# amp_board.net
KiCad netlist of a schematic drawn in EAGLE
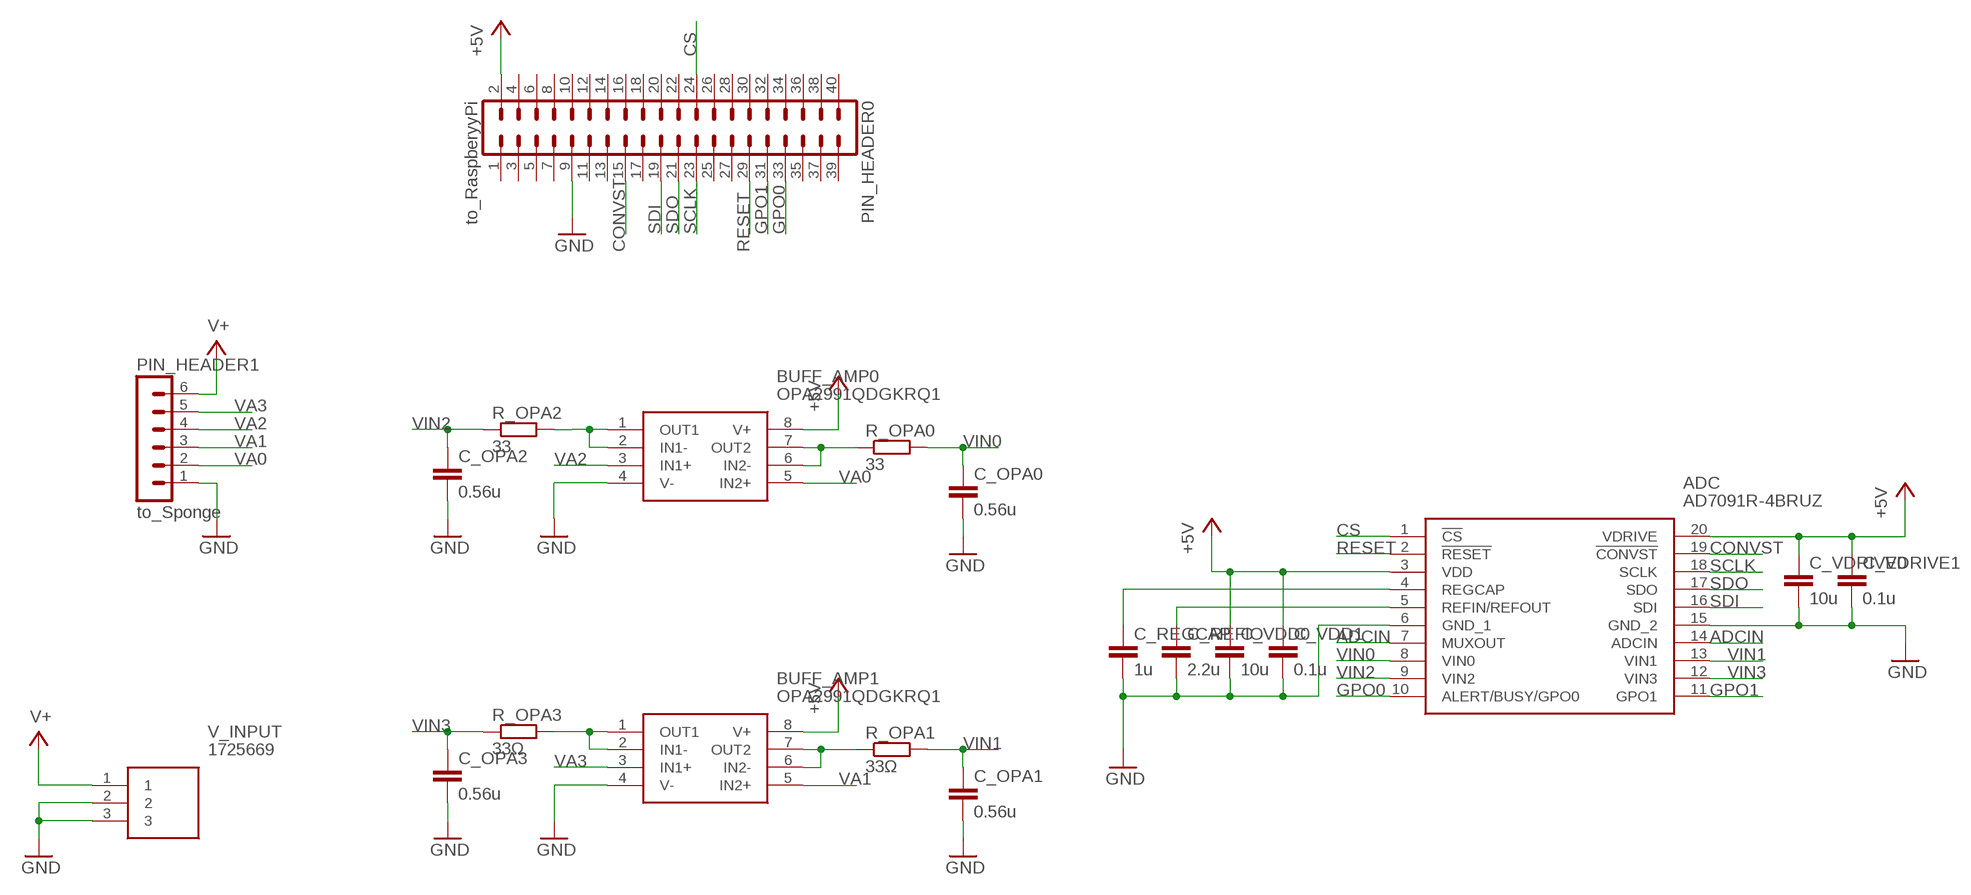
[diagram p0: schematic, sheet 1]

(export (version "E")
  (design (tool "Eeschema 10.0.6"))
  (components
    (comp (ref "ADC")
      (value "AD7091R-4BRUZ")
      (footprint "eagle-import:SOP65P640X120-20N")
      (fields (field (name "RS_PART_NUMBER") "8107727P"))
      (libsource (lib "eagle-import") (part "AD7091R-4BRUZ"))
    )
    (comp (ref "BUFF_AMP0")
      (value "OPA2991QDGKRQ1")
      (footprint "eagle-import:SOP65P490X110-8N")
      (libsource (lib "eagle-import") (part "OPA2991QDGKRQ1"))
    )
    (comp (ref "BUFF_AMP1")
      (value "OPA2991QDGKRQ1")
      (footprint "eagle-import:SOP65P490X110-8N")
      (libsource (lib "eagle-import") (part "OPA2991QDGKRQ1"))
    )
    (comp (ref "C_OPA0")
      (value "0.56u")
      (footprint "eagle-import:C0805")
      (libsource (lib "eagle-import") (part "C-EUC0805"))
    )
    (comp (ref "C_OPA1")
      (value "0.56u")
      (footprint "eagle-import:C0805")
      (libsource (lib "eagle-import") (part "C-EUC0805"))
    )
    (comp (ref "C_OPA2")
      (value "0.56u")
      (footprint "eagle-import:C0805")
      (libsource (lib "eagle-import") (part "C-EUC0805"))
    )
    (comp (ref "C_OPA3")
      (value "0.56u")
      (footprint "eagle-import:C0805")
      (libsource (lib "eagle-import") (part "C-EUC0805"))
    )
    (comp (ref "C_REFIO")
      (value "2.2u")
      (footprint "eagle-import:C0805")
      (libsource (lib "eagle-import") (part "C-EUC0805"))
    )
    (comp (ref "C_REGCAP")
      (value "1u")
      (footprint "eagle-import:C0805")
      (libsource (lib "eagle-import") (part "C-EUC0805"))
    )
    (comp (ref "C_VDD0")
      (value "10u")
      (footprint "eagle-import:C0805")
      (libsource (lib "eagle-import") (part "C-EUC0805"))
    )
    (comp (ref "C_VDD1")
      (value "0.1u")
      (footprint "eagle-import:C0805")
      (libsource (lib "eagle-import") (part "C-EUC0805"))
    )
    (comp (ref "C_VDRIVE0")
      (value "10u")
      (footprint "eagle-import:C0805")
      (libsource (lib "eagle-import") (part "C-EUC0805"))
    )
    (comp (ref "C_VDRIVE1")
      (value "0.1u")
      (footprint "eagle-import:C0805")
      (libsource (lib "eagle-import") (part "C-EUC0805"))
    )
    (comp (ref "PIN_HEADER0")
      (value "to_RaspberyyPi")
      (footprint "eagle-import:MA20-2")
      (libsource (lib "eagle-import") (part "MA20-2"))
    )
    (comp (ref "PIN_HEADER1")
      (value "to_Sponge")
      (footprint "eagle-import:MA06-1")
      (libsource (lib "eagle-import") (part "MA06-1"))
    )
    (comp (ref "R_OPA0")
      (value "33")
      (footprint "eagle-import:R1206")
      (libsource (lib "eagle-import") (part "R-EU_R1206"))
    )
    (comp (ref "R_OPA1")
      (value "33Ω")
      (footprint "eagle-import:R1206")
      (libsource (lib "eagle-import") (part "R-EU_R1206"))
    )
    (comp (ref "R_OPA2")
      (value "33")
      (footprint "eagle-import:R1206")
      (libsource (lib "eagle-import") (part "R-EU_R1206"))
    )
    (comp (ref "R_OPA3")
      (value "33Ω")
      (footprint "eagle-import:R1206")
      (libsource (lib "eagle-import") (part "R-EU_R1206"))
    )
    (comp (ref "V_INPUT")
      (value "1725669")
      (footprint "eagle-import:1725669")
      (fields (field (name "MOUSER_PART_NUMBER") "651-1725669"))
      (libsource (lib "eagle-import") (part "1725669"))
    )
  )
  (nets
    (net (code "1") (name "+5V") (class "Default")
      (node (ref "ADC") (pin "20") (pinfunction "VDRIVE_20") (pintype "bidirectional"))
      (node (ref "ADC") (pin "3") (pinfunction "VDD_3") (pintype "bidirectional"))
      (node (ref "BUFF_AMP0") (pin "8") (pinfunction "V+_8") (pintype "bidirectional"))
      (node (ref "BUFF_AMP1") (pin "8") (pinfunction "V+_8") (pintype "bidirectional"))
      (node (ref "C_VDD0") (pin "1") (pinfunction "1_1") (pintype "passive"))
      (node (ref "C_VDD1") (pin "1") (pinfunction "1_1") (pintype "passive"))
      (node (ref "C_VDRIVE0") (pin "1") (pinfunction "1_1") (pintype "passive"))
      (node (ref "C_VDRIVE1") (pin "1") (pinfunction "1_1") (pintype "passive"))
      (node (ref "PIN_HEADER0") (pin "2") (pinfunction "2_2") (pintype "passive"))
    )
    (net (code "2") (name "/ADCIN") (class "Default")
      (node (ref "ADC") (pin "14") (pinfunction "ADCIN_14") (pintype "bidirectional"))
      (node (ref "ADC") (pin "7") (pinfunction "MUXOUT_7") (pintype "bidirectional"))
    )
    (net (code "3") (name "/CONVST") (class "Default")
      (node (ref "ADC") (pin "19") (pinfunction "~{CONVST}_19") (pintype "bidirectional"))
      (node (ref "PIN_HEADER0") (pin "15") (pinfunction "15_15") (pintype "passive"))
    )
    (net (code "4") (name "/CS") (class "Default")
      (node (ref "ADC") (pin "1") (pinfunction "~{CS}_1") (pintype "bidirectional"))
      (node (ref "PIN_HEADER0") (pin "24") (pinfunction "24_24") (pintype "passive"))
    )
    (net (code "5") (name "/GPO0") (class "Default")
      (node (ref "ADC") (pin "10") (pinfunction "ALERT/BUSY/GPO0_10") (pintype "bidirectional"))
      (node (ref "PIN_HEADER0") (pin "33") (pinfunction "33_33") (pintype "passive"))
    )
    (net (code "6") (name "/GPO1") (class "Default")
      (node (ref "ADC") (pin "11") (pinfunction "GPO1_11") (pintype "bidirectional"))
      (node (ref "PIN_HEADER0") (pin "31") (pinfunction "31_31") (pintype "passive"))
    )
    (net (code "7") (name "/RESET") (class "Default")
      (node (ref "ADC") (pin "2") (pinfunction "~{RESET}_2") (pintype "bidirectional"))
      (node (ref "PIN_HEADER0") (pin "29") (pinfunction "29_29") (pintype "passive"))
    )
    (net (code "8") (name "/SCLK") (class "Default")
      (node (ref "ADC") (pin "18") (pinfunction "SCLK_18") (pintype "bidirectional"))
      (node (ref "PIN_HEADER0") (pin "23") (pinfunction "23_23") (pintype "passive"))
    )
    (net (code "9") (name "/SDI") (class "Default")
      (node (ref "ADC") (pin "16") (pinfunction "SDI_16") (pintype "bidirectional"))
      (node (ref "PIN_HEADER0") (pin "19") (pinfunction "19_19") (pintype "passive"))
    )
    (net (code "10") (name "/SDO") (class "Default")
      (node (ref "ADC") (pin "17") (pinfunction "SDO_17") (pintype "bidirectional"))
      (node (ref "PIN_HEADER0") (pin "21") (pinfunction "21_21") (pintype "passive"))
    )
    (net (code "11") (name "/VA0") (class "Default")
      (node (ref "BUFF_AMP0") (pin "5") (pinfunction "IN2+_5") (pintype "bidirectional"))
      (node (ref "PIN_HEADER1") (pin "2") (pinfunction "2_2") (pintype "passive"))
    )
    (net (code "12") (name "/VA1") (class "Default")
      (node (ref "BUFF_AMP1") (pin "5") (pinfunction "IN2+_5") (pintype "bidirectional"))
      (node (ref "PIN_HEADER1") (pin "3") (pinfunction "3_3") (pintype "passive"))
    )
    (net (code "13") (name "/VA2") (class "Default")
      (node (ref "BUFF_AMP0") (pin "3") (pinfunction "IN1+_3") (pintype "bidirectional"))
      (node (ref "PIN_HEADER1") (pin "4") (pinfunction "4_4") (pintype "passive"))
    )
    (net (code "14") (name "/VA3") (class "Default")
      (node (ref "BUFF_AMP1") (pin "3") (pinfunction "IN1+_3") (pintype "bidirectional"))
      (node (ref "PIN_HEADER1") (pin "5") (pinfunction "5_5") (pintype "passive"))
    )
    (net (code "15") (name "/VIN0") (class "Default")
      (node (ref "ADC") (pin "8") (pinfunction "VIN0_8") (pintype "bidirectional"))
      (node (ref "C_OPA0") (pin "1") (pinfunction "1_1") (pintype "passive"))
      (node (ref "R_OPA0") (pin "2") (pinfunction "2_2") (pintype "passive"))
    )
    (net (code "16") (name "/VIN1") (class "Default")
      (node (ref "ADC") (pin "13") (pinfunction "VIN1_13") (pintype "bidirectional"))
      (node (ref "C_OPA1") (pin "1") (pinfunction "1_1") (pintype "passive"))
      (node (ref "R_OPA1") (pin "2") (pinfunction "2_2") (pintype "passive"))
    )
    (net (code "17") (name "/VIN2") (class "Default")
      (node (ref "ADC") (pin "9") (pinfunction "VIN2_9") (pintype "bidirectional"))
      (node (ref "C_OPA2") (pin "1") (pinfunction "1_1") (pintype "passive"))
      (node (ref "R_OPA2") (pin "1") (pinfunction "1_1") (pintype "passive"))
    )
    (net (code "18") (name "/VIN3") (class "Default")
      (node (ref "ADC") (pin "12") (pinfunction "VIN3_12") (pintype "bidirectional"))
      (node (ref "C_OPA3") (pin "1") (pinfunction "1_1") (pintype "passive"))
      (node (ref "R_OPA3") (pin "1") (pinfunction "1_1") (pintype "passive"))
    )
    (net (code "19") (name "GND") (class "Default")
      (node (ref "ADC") (pin "15") (pinfunction "GND_2_15") (pintype "bidirectional"))
      (node (ref "ADC") (pin "6") (pinfunction "GND_1_6") (pintype "bidirectional"))
      (node (ref "BUFF_AMP0") (pin "4") (pinfunction "V-_4") (pintype "bidirectional"))
      (node (ref "BUFF_AMP1") (pin "4") (pinfunction "V-_4") (pintype "bidirectional"))
      (node (ref "C_OPA0") (pin "2") (pinfunction "2_2") (pintype "passive"))
      (node (ref "C_OPA1") (pin "2") (pinfunction "2_2") (pintype "passive"))
      (node (ref "C_OPA2") (pin "2") (pinfunction "2_2") (pintype "passive"))
      (node (ref "C_OPA3") (pin "2") (pinfunction "2_2") (pintype "passive"))
      (node (ref "C_REFIO") (pin "2") (pinfunction "2_2") (pintype "passive"))
      (node (ref "C_REGCAP") (pin "2") (pinfunction "2_2") (pintype "passive"))
      (node (ref "C_VDD0") (pin "2") (pinfunction "2_2") (pintype "passive"))
      (node (ref "C_VDD1") (pin "2") (pinfunction "2_2") (pintype "passive"))
      (node (ref "C_VDRIVE0") (pin "2") (pinfunction "2_2") (pintype "passive"))
      (node (ref "C_VDRIVE1") (pin "2") (pinfunction "2_2") (pintype "passive"))
      (node (ref "PIN_HEADER0") (pin "9") (pinfunction "9_9") (pintype "passive"))
      (node (ref "PIN_HEADER1") (pin "1") (pinfunction "1_1") (pintype "passive"))
      (node (ref "V_INPUT") (pin "2") (pinfunction "2_2") (pintype "bidirectional"))
      (node (ref "V_INPUT") (pin "3") (pinfunction "3_3") (pintype "bidirectional"))
    )
    (net (code "20") (name "Net-(ADC-REFIN{slash}REFOUT)") (class "Default")
      (node (ref "ADC") (pin "5") (pinfunction "REFIN/REFOUT_5") (pintype "bidirectional"))
      (node (ref "C_REFIO") (pin "1") (pinfunction "1_1") (pintype "passive"))
    )
    (net (code "21") (name "Net-(ADC-REGCAP)") (class "Default")
      (node (ref "ADC") (pin "4") (pinfunction "REGCAP_4") (pintype "bidirectional"))
      (node (ref "C_REGCAP") (pin "1") (pinfunction "1_1") (pintype "passive"))
    )
    (net (code "22") (name "Net-(BUFF_AMP0-IN1-)") (class "Default")
      (node (ref "BUFF_AMP0") (pin "1") (pinfunction "OUT1_1") (pintype "bidirectional"))
      (node (ref "BUFF_AMP0") (pin "2") (pinfunction "IN1-_2") (pintype "bidirectional"))
      (node (ref "R_OPA2") (pin "2") (pinfunction "2_2") (pintype "passive"))
    )
    (net (code "23") (name "Net-(BUFF_AMP0-IN2-)") (class "Default")
      (node (ref "BUFF_AMP0") (pin "6") (pinfunction "IN2-_6") (pintype "bidirectional"))
      (node (ref "BUFF_AMP0") (pin "7") (pinfunction "OUT2_7") (pintype "bidirectional"))
      (node (ref "R_OPA0") (pin "1") (pinfunction "1_1") (pintype "passive"))
    )
    (net (code "24") (name "Net-(BUFF_AMP1-IN1-)") (class "Default")
      (node (ref "BUFF_AMP1") (pin "1") (pinfunction "OUT1_1") (pintype "bidirectional"))
      (node (ref "BUFF_AMP1") (pin "2") (pinfunction "IN1-_2") (pintype "bidirectional"))
      (node (ref "R_OPA3") (pin "2") (pinfunction "2_2") (pintype "passive"))
    )
    (net (code "25") (name "Net-(BUFF_AMP1-IN2-)") (class "Default")
      (node (ref "BUFF_AMP1") (pin "6") (pinfunction "IN2-_6") (pintype "bidirectional"))
      (node (ref "BUFF_AMP1") (pin "7") (pinfunction "OUT2_7") (pintype "bidirectional"))
      (node (ref "R_OPA1") (pin "1") (pinfunction "1_1") (pintype "passive"))
    )
    (net (code "26") (name "V+") (class "Default")
      (node (ref "PIN_HEADER1") (pin "6") (pinfunction "6_6") (pintype "passive"))
      (node (ref "V_INPUT") (pin "1") (pinfunction "1_1") (pintype "bidirectional"))
    )
    (net (code "27") (name "unconnected-(PIN_HEADER0-Pad1)") (class "Default")
      (node (ref "PIN_HEADER0") (pin "1") (pinfunction "1_1") (pintype "passive"))
    )
    (net (code "28") (name "unconnected-(PIN_HEADER0-Pad3)") (class "Default")
      (node (ref "PIN_HEADER0") (pin "3") (pinfunction "3_3") (pintype "passive"))
    )
    (net (code "29") (name "unconnected-(PIN_HEADER0-Pad4)") (class "Default")
      (node (ref "PIN_HEADER0") (pin "4") (pinfunction "4_4") (pintype "passive"))
    )
    (net (code "30") (name "unconnected-(PIN_HEADER0-Pad5)") (class "Default")
      (node (ref "PIN_HEADER0") (pin "5") (pinfunction "5_5") (pintype "passive"))
    )
    (net (code "31") (name "unconnected-(PIN_HEADER0-Pad6)") (class "Default")
      (node (ref "PIN_HEADER0") (pin "6") (pinfunction "6_6") (pintype "passive"))
    )
    (net (code "32") (name "unconnected-(PIN_HEADER0-Pad7)") (class "Default")
      (node (ref "PIN_HEADER0") (pin "7") (pinfunction "7_7") (pintype "passive"))
    )
    (net (code "33") (name "unconnected-(PIN_HEADER0-Pad8)") (class "Default")
      (node (ref "PIN_HEADER0") (pin "8") (pinfunction "8_8") (pintype "passive"))
    )
    (net (code "34") (name "unconnected-(PIN_HEADER0-Pad10)") (class "Default")
      (node (ref "PIN_HEADER0") (pin "10") (pinfunction "10_10") (pintype "passive"))
    )
    (net (code "35") (name "unconnected-(PIN_HEADER0-Pad11)") (class "Default")
      (node (ref "PIN_HEADER0") (pin "11") (pinfunction "11_11") (pintype "passive"))
    )
    (net (code "36") (name "unconnected-(PIN_HEADER0-Pad12)") (class "Default")
      (node (ref "PIN_HEADER0") (pin "12") (pinfunction "12_12") (pintype "passive"))
    )
    (net (code "37") (name "unconnected-(PIN_HEADER0-Pad13)") (class "Default")
      (node (ref "PIN_HEADER0") (pin "13") (pinfunction "13_13") (pintype "passive"))
    )
    (net (code "38") (name "unconnected-(PIN_HEADER0-Pad14)") (class "Default")
      (node (ref "PIN_HEADER0") (pin "14") (pinfunction "14_14") (pintype "passive"))
    )
    (net (code "39") (name "unconnected-(PIN_HEADER0-Pad16)") (class "Default")
      (node (ref "PIN_HEADER0") (pin "16") (pinfunction "16_16") (pintype "passive"))
    )
    (net (code "40") (name "unconnected-(PIN_HEADER0-Pad17)") (class "Default")
      (node (ref "PIN_HEADER0") (pin "17") (pinfunction "17_17") (pintype "passive"))
    )
    (net (code "41") (name "unconnected-(PIN_HEADER0-Pad18)") (class "Default")
      (node (ref "PIN_HEADER0") (pin "18") (pinfunction "18_18") (pintype "passive"))
    )
    (net (code "42") (name "unconnected-(PIN_HEADER0-Pad20)") (class "Default")
      (node (ref "PIN_HEADER0") (pin "20") (pinfunction "20_20") (pintype "passive"))
    )
    (net (code "43") (name "unconnected-(PIN_HEADER0-Pad22)") (class "Default")
      (node (ref "PIN_HEADER0") (pin "22") (pinfunction "22_22") (pintype "passive"))
    )
    (net (code "44") (name "unconnected-(PIN_HEADER0-Pad25)") (class "Default")
      (node (ref "PIN_HEADER0") (pin "25") (pinfunction "25_25") (pintype "passive"))
    )
    (net (code "45") (name "unconnected-(PIN_HEADER0-Pad26)") (class "Default")
      (node (ref "PIN_HEADER0") (pin "26") (pinfunction "26_26") (pintype "passive"))
    )
    (net (code "46") (name "unconnected-(PIN_HEADER0-Pad27)") (class "Default")
      (node (ref "PIN_HEADER0") (pin "27") (pinfunction "27_27") (pintype "passive"))
    )
    (net (code "47") (name "unconnected-(PIN_HEADER0-Pad28)") (class "Default")
      (node (ref "PIN_HEADER0") (pin "28") (pinfunction "28_28") (pintype "passive"))
    )
    (net (code "48") (name "unconnected-(PIN_HEADER0-Pad30)") (class "Default")
      (node (ref "PIN_HEADER0") (pin "30") (pinfunction "30_30") (pintype "passive"))
    )
    (net (code "49") (name "unconnected-(PIN_HEADER0-Pad32)") (class "Default")
      (node (ref "PIN_HEADER0") (pin "32") (pinfunction "32_32") (pintype "passive"))
    )
    (net (code "50") (name "unconnected-(PIN_HEADER0-Pad34)") (class "Default")
      (node (ref "PIN_HEADER0") (pin "34") (pinfunction "34_34") (pintype "passive"))
    )
    (net (code "51") (name "unconnected-(PIN_HEADER0-Pad35)") (class "Default")
      (node (ref "PIN_HEADER0") (pin "35") (pinfunction "35_35") (pintype "passive"))
    )
    (net (code "52") (name "unconnected-(PIN_HEADER0-Pad36)") (class "Default")
      (node (ref "PIN_HEADER0") (pin "36") (pinfunction "36_36") (pintype "passive"))
    )
    (net (code "53") (name "unconnected-(PIN_HEADER0-Pad37)") (class "Default")
      (node (ref "PIN_HEADER0") (pin "37") (pinfunction "37_37") (pintype "passive"))
    )
    (net (code "54") (name "unconnected-(PIN_HEADER0-Pad38)") (class "Default")
      (node (ref "PIN_HEADER0") (pin "38") (pinfunction "38_38") (pintype "passive"))
    )
    (net (code "55") (name "unconnected-(PIN_HEADER0-Pad39)") (class "Default")
      (node (ref "PIN_HEADER0") (pin "39") (pinfunction "39_39") (pintype "passive"))
    )
    (net (code "56") (name "unconnected-(PIN_HEADER0-Pad40)") (class "Default")
      (node (ref "PIN_HEADER0") (pin "40") (pinfunction "40_40") (pintype "passive"))
    )
  )
)
